# Wi-Fi.net
KiCad netlist of a schematic drawn in Altium Designer
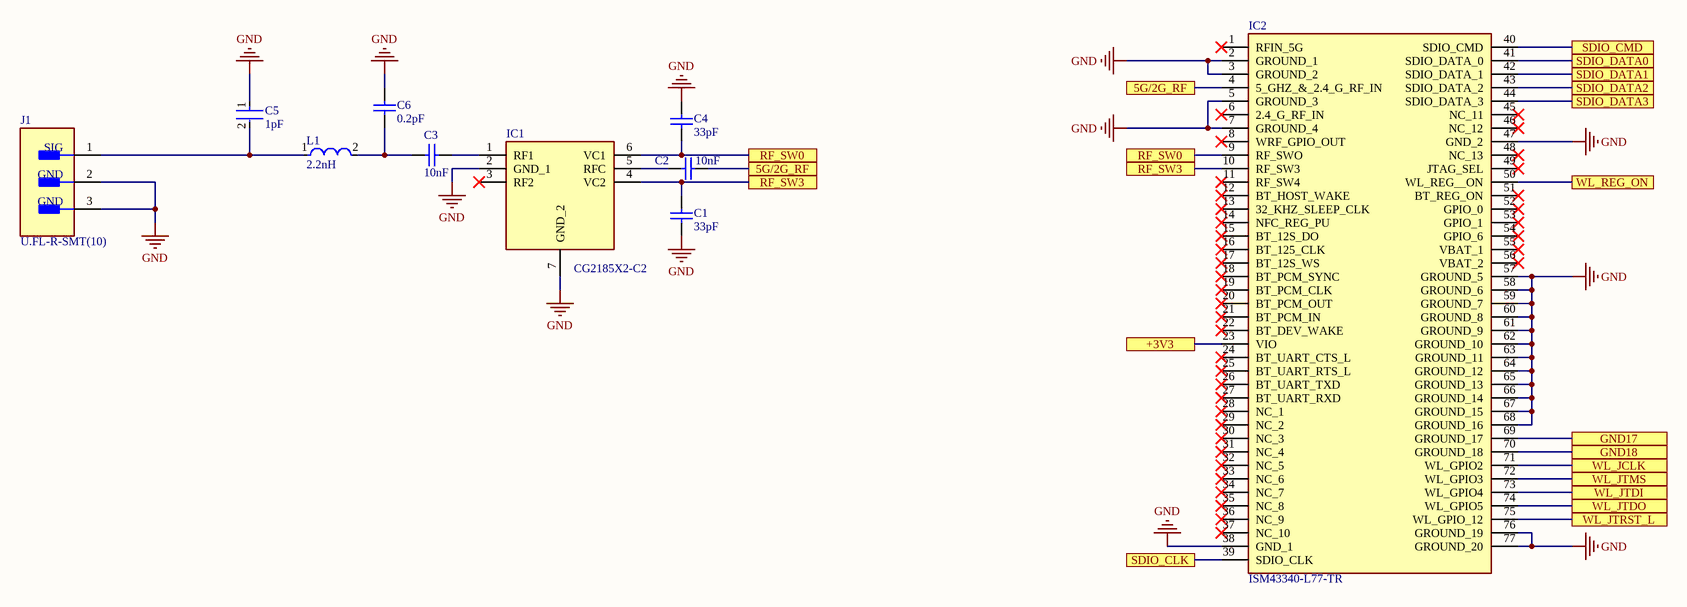
[diagram p0: Wi-Fi.schdoc]

(export (version "E")
  (design (tool "Eeschema 10.0.6"))
  (components
    (comp (ref "C1")
      (value "33pF")
      (footprint "CAPC1005X56X25ML10T15")
      (fields
        (field (name "MANUFACTURER") "AVX Interconnect / Elco")
        (field (name "PART NUMBER") "04025A330JAT2A")
      )
      (libsource (lib "Altium Content Vault") (part "CAP"))
    )
    (comp (ref "C2")
      (value "10nF")
      (footprint "CAPC1608X90X35ML10T15")
      (description "Chip Capacitor, 10 nF, +/- 10%, 50 V, -55 to 125 degC, 0603 (1608 Metric), RoHS, Tape and Reel")
      (fields (field (name "VOLTAGE") "50V") (field (name "TOLERANCE") "10%"))
      (libsource (lib "Altium Content Vault") (part "CAP-NP-2"))
    )
    (comp (ref "C3")
      (value "10nF")
      (footprint "CAPC1608X90X35ML10T15")
      (description "Chip Capacitor, 10 nF, +/- 10%, 50 V, -55 to 125 degC, 0603 (1608 Metric), RoHS, Tape and Reel")
      (fields (field (name "VOLTAGE") "50V") (field (name "TOLERANCE") "10%"))
      (libsource (lib "Altium Content Vault") (part "CAP-NP-2"))
    )
    (comp (ref "C4")
      (value "33pF")
      (footprint "CAPC1005X56X25ML10T15")
      (fields
        (field (name "MANUFACTURER") "AVX Interconnect / Elco")
        (field (name "PART NUMBER") "04025A330JAT2A")
      )
      (libsource (lib "Altium Content Vault") (part "CAP"))
    )
    (comp (ref "C5")
      (value "1pF")
      (footprint "FP-GJM155-0_05-IPC_B")
      (description "Multi-Layer Ceramic Capacitor 1pF C0G  ±0.1pF 0402 Paper T/R")
      (fields (field (name "VOLTAGE") "50V"))
      (libsource (lib "Altium Content Vault") (part "02cd4be3c70576c341d710602a673aa"))
    )
    (comp (ref "C6")
      (value "0.2pF")
      (footprint "CAPC1608X74X38NL10T13")
      (fields
        (field (name "MANUFACTURER") "AVX Interconnect / Elco")
        (field (name "PART NUMBER") "ML03V10R2BAT2A")
      )
      (libsource (lib "Altium Content Vault") (part "CAP"))
    )
    (comp (ref "IC1")
      (value "CG2185X2-C2")
      (footprint "SamacSys:SON35P100X100X37-7N")
      (description "Integrated Circuit")
      (libsource (lib "*") (part "CG2185X2-C2"))
    )
    (comp (ref "IC2")
      (value "ISM43340-L77-TR")
      (footprint "SamacSys:ISM43340L77TR")
      (description "Integrated Circuit")
      (fields (field (name "MOUSER PART NUMBER") "347-ISM43340L77TR"))
      (libsource (lib "SamacSys") (part "ISM43340-L77-TR"))
    )
    (comp (ref "J1")
      (value "U.FL-R-SMT(10)")
      (footprint "FP-U_FL-R-SMT_10-MFG")
      (description "CONN U.FL RCPT STR 50 OHM SMD")
      (libsource (lib "Altium Content Vault") (part "eef6fde44c591823e8076210edfe12f"))
    )
    (comp (ref "L1")
      (value "2.2nH")
      (footprint "FP-LQW15AN_00-W0_6-0_1-MFG")
      (description "Wire Wound RF Inductor 2.2nH ±0.2nH 1000mA 0.027Ω 0402 (1005)")
      (libsource (lib "Altium Content Vault") (part "725321dda6339637d4d059423bc1c3c"))
    )
  )
  (nets
    (net (code "1") (name "/+3V3") (class "Default")
      (node (ref "IC2") (pin "23") (pinfunction "VIO_23") (pintype "passive"))
    )
    (net (code "2") (name "/5G{slash}2G_RF") (class "Default")
      (node (ref "C2") (pin "2") (pinfunction "2_2") (pintype "passive"))
      (node (ref "IC2") (pin "4") (pinfunction "5_GHZ_&_2.4_G_RF_IN_4") (pintype "passive"))
    )
    (net (code "3") (name "/GND17") (class "Default")
      (node (ref "IC2") (pin "69") (pinfunction "GROUND_17_69") (pintype "passive"))
    )
    (net (code "4") (name "/GND18") (class "Default")
      (node (ref "IC2") (pin "70") (pinfunction "GROUND_18_70") (pintype "passive"))
    )
    (net (code "5") (name "/RF_SW0") (class "Default")
      (node (ref "C4") (pin "1") (pinfunction "1_1") (pintype "passive"))
      (node (ref "IC1") (pin "6") (pinfunction "VC1_6") (pintype "passive"))
      (node (ref "IC2") (pin "9") (pinfunction "RF_SWO_9") (pintype "passive"))
    )
    (net (code "6") (name "/RF_SW3") (class "Default")
      (node (ref "C1") (pin "2") (pinfunction "2_2") (pintype "passive"))
      (node (ref "IC1") (pin "4") (pinfunction "VC2_4") (pintype "passive"))
      (node (ref "IC2") (pin "10") (pinfunction "RF_SW3_10") (pintype "passive"))
    )
    (net (code "7") (name "/SDIO_CLK") (class "Default")
      (node (ref "IC2") (pin "39") (pinfunction "SDIO_CLK_39") (pintype "passive"))
    )
    (net (code "8") (name "/SDIO_CMD") (class "Default")
      (node (ref "IC2") (pin "40") (pinfunction "SDIO_CMD_40") (pintype "passive"))
    )
    (net (code "9") (name "/SDIO_DATA0") (class "Default")
      (node (ref "IC2") (pin "41") (pinfunction "SDIO_DATA_0_41") (pintype "passive"))
    )
    (net (code "10") (name "/SDIO_DATA1") (class "Default")
      (node (ref "IC2") (pin "42") (pinfunction "SDIO_DATA_1_42") (pintype "passive"))
    )
    (net (code "11") (name "/SDIO_DATA2") (class "Default")
      (node (ref "IC2") (pin "43") (pinfunction "SDIO_DATA_2_43") (pintype "passive"))
    )
    (net (code "12") (name "/SDIO_DATA3") (class "Default")
      (node (ref "IC2") (pin "44") (pinfunction "SDIO_DATA_3_44") (pintype "passive"))
    )
    (net (code "13") (name "/WL_JCLK") (class "Default")
      (node (ref "IC2") (pin "71") (pinfunction "WL_GPIO2_71") (pintype "passive"))
    )
    (net (code "14") (name "/WL_JTDI") (class "Default")
      (node (ref "IC2") (pin "73") (pinfunction "WL_GPIO4_73") (pintype "passive"))
    )
    (net (code "15") (name "/WL_JTDO") (class "Default")
      (node (ref "IC2") (pin "74") (pinfunction "WL_GPIO5_74") (pintype "passive"))
    )
    (net (code "16") (name "/WL_JTMS") (class "Default")
      (node (ref "IC2") (pin "72") (pinfunction "WL_GPIO3_72") (pintype "passive"))
    )
    (net (code "17") (name "/WL_JTRST_L") (class "Default")
      (node (ref "IC2") (pin "75") (pinfunction "WL_GPIO_12_75") (pintype "passive"))
    )
    (net (code "18") (name "/WL_REG_ON") (class "Default")
      (node (ref "IC2") (pin "50") (pinfunction "WL_REG__ON_50") (pintype "passive"))
    )
    (net (code "19") (name "GND") (class "Default")
      (node (ref "C1") (pin "1") (pinfunction "1_1") (pintype "passive"))
      (node (ref "C4") (pin "2") (pinfunction "2_2") (pintype "passive"))
      (node (ref "C5") (pin "1") (pinfunction "1_1") (pintype "passive"))
      (node (ref "C6") (pin "2") (pinfunction "2_2") (pintype "passive"))
      (node (ref "IC1") (pin "2") (pinfunction "GND_1_2") (pintype "passive"))
      (node (ref "IC1") (pin "7") (pinfunction "GND_2_7") (pintype "passive"))
      (node (ref "IC2") (pin "2") (pinfunction "GROUND_1_2") (pintype "passive"))
      (node (ref "IC2") (pin "3") (pinfunction "GROUND_2_3") (pintype "passive"))
      (node (ref "IC2") (pin "38") (pinfunction "GND_1_38") (pintype "passive"))
      (node (ref "IC2") (pin "47") (pinfunction "GND_2_47") (pintype "passive"))
      (node (ref "IC2") (pin "5") (pinfunction "GROUND_3_5") (pintype "passive"))
      (node (ref "IC2") (pin "57") (pinfunction "GROUND_5_57") (pintype "passive"))
      (node (ref "IC2") (pin "58") (pinfunction "GROUND_6_58") (pintype "passive"))
      (node (ref "IC2") (pin "59") (pinfunction "GROUND_7_59") (pintype "passive"))
      (node (ref "IC2") (pin "60") (pinfunction "GROUND_8_60") (pintype "passive"))
      (node (ref "IC2") (pin "61") (pinfunction "GROUND_9_61") (pintype "passive"))
      (node (ref "IC2") (pin "62") (pinfunction "GROUND_10_62") (pintype "passive"))
      (node (ref "IC2") (pin "63") (pinfunction "GROUND_11_63") (pintype "passive"))
      (node (ref "IC2") (pin "64") (pinfunction "GROUND_12_64") (pintype "passive"))
      (node (ref "IC2") (pin "65") (pinfunction "GROUND_13_65") (pintype "passive"))
      (node (ref "IC2") (pin "66") (pinfunction "GROUND_14_66") (pintype "passive"))
      (node (ref "IC2") (pin "67") (pinfunction "GROUND_15_67") (pintype "passive"))
      (node (ref "IC2") (pin "68") (pinfunction "GROUND_16_68") (pintype "passive"))
      (node (ref "IC2") (pin "7") (pinfunction "GROUND_4_7") (pintype "passive"))
      (node (ref "IC2") (pin "76") (pinfunction "GROUND_19_76") (pintype "passive"))
      (node (ref "IC2") (pin "77") (pinfunction "GROUND_20_77") (pintype "passive"))
      (node (ref "J1") (pin "2") (pinfunction "GND_2") (pintype "power_in"))
      (node (ref "J1") (pin "3") (pinfunction "GND_3") (pintype "power_in"))
    )
    (net (code "20") (name "Net-(C3-Pad1)") (class "Default")
      (node (ref "C3") (pin "1") (pinfunction "1_1") (pintype "passive"))
      (node (ref "C6") (pin "1") (pinfunction "1_1") (pintype "passive"))
      (node (ref "L1") (pin "2") (pinfunction "2_2") (pintype "passive"))
    )
    (net (code "21") (name "Net-(IC1-RF1)") (class "Default")
      (node (ref "C3") (pin "2") (pinfunction "2_2") (pintype "passive"))
      (node (ref "IC1") (pin "1") (pinfunction "RF1_1") (pintype "passive"))
    )
    (net (code "22") (name "Net-(IC1-RFC)") (class "Default")
      (node (ref "C2") (pin "1") (pinfunction "1_1") (pintype "passive"))
      (node (ref "IC1") (pin "5") (pinfunction "RFC_5") (pintype "passive"))
    )
    (net (code "23") (name "Net-(J1-SIG)") (class "Default")
      (node (ref "C5") (pin "2") (pinfunction "2_2") (pintype "passive"))
      (node (ref "J1") (pin "1") (pinfunction "SIG_1") (pintype "passive"))
      (node (ref "L1") (pin "1") (pinfunction "1_1") (pintype "passive"))
    )
    (net (code "24") (name "unconnected-(IC1-RF2-Pad3)") (class "Default")
      (node (ref "IC1") (pin "3") (pinfunction "RF2_3") (pintype "passive+no_connect"))
    )
    (net (code "25") (name "unconnected-(IC2-2.4_G_RF_IN-Pad6)") (class "Default")
      (node (ref "IC2") (pin "6") (pinfunction "2.4_G_RF_IN_6") (pintype "passive+no_connect"))
    )
    (net (code "26") (name "unconnected-(IC2-32_KHZ_SLEEP_CLK-Pad13)") (class "Default")
      (node (ref "IC2") (pin "13") (pinfunction "32_KHZ_SLEEP_CLK_13") (pintype "passive+no_connect"))
    )
    (net (code "27") (name "unconnected-(IC2-BT_12S_DO-Pad15)") (class "Default")
      (node (ref "IC2") (pin "15") (pinfunction "BT_12S_DO_15") (pintype "passive+no_connect"))
    )
    (net (code "28") (name "unconnected-(IC2-BT_12S_WS-Pad17)") (class "Default")
      (node (ref "IC2") (pin "17") (pinfunction "BT_12S_WS_17") (pintype "passive+no_connect"))
    )
    (net (code "29") (name "unconnected-(IC2-BT_125_CLK-Pad16)") (class "Default")
      (node (ref "IC2") (pin "16") (pinfunction "BT_125_CLK_16") (pintype "passive+no_connect"))
    )
    (net (code "30") (name "unconnected-(IC2-BT_DEV_WAKE-Pad22)") (class "Default")
      (node (ref "IC2") (pin "22") (pinfunction "BT_DEV_WAKE_22") (pintype "passive+no_connect"))
    )
    (net (code "31") (name "unconnected-(IC2-BT_HOST_WAKE-Pad12)") (class "Default")
      (node (ref "IC2") (pin "12") (pinfunction "BT_HOST_WAKE_12") (pintype "passive+no_connect"))
    )
    (net (code "32") (name "unconnected-(IC2-BT_PCM_CLK-Pad19)") (class "Default")
      (node (ref "IC2") (pin "19") (pinfunction "BT_PCM_CLK_19") (pintype "passive+no_connect"))
    )
    (net (code "33") (name "unconnected-(IC2-BT_PCM_IN-Pad21)") (class "Default")
      (node (ref "IC2") (pin "21") (pinfunction "BT_PCM_IN_21") (pintype "passive+no_connect"))
    )
    (net (code "34") (name "unconnected-(IC2-BT_PCM_OUT-Pad20)") (class "Default")
      (node (ref "IC2") (pin "20") (pinfunction "BT_PCM_OUT_20") (pintype "passive+no_connect"))
    )
    (net (code "35") (name "unconnected-(IC2-BT_PCM_SYNC-Pad18)") (class "Default")
      (node (ref "IC2") (pin "18") (pinfunction "BT_PCM_SYNC_18") (pintype "passive+no_connect"))
    )
    (net (code "36") (name "unconnected-(IC2-BT_REG_ON-Pad51)") (class "Default")
      (node (ref "IC2") (pin "51") (pinfunction "BT_REG_ON_51") (pintype "passive+no_connect"))
    )
    (net (code "37") (name "unconnected-(IC2-BT_UART_CTS_L-Pad24)") (class "Default")
      (node (ref "IC2") (pin "24") (pinfunction "BT_UART_CTS_L_24") (pintype "passive+no_connect"))
    )
    (net (code "38") (name "unconnected-(IC2-BT_UART_RTS_L-Pad25)") (class "Default")
      (node (ref "IC2") (pin "25") (pinfunction "BT_UART_RTS_L_25") (pintype "passive+no_connect"))
    )
    (net (code "39") (name "unconnected-(IC2-BT_UART_RXD-Pad27)") (class "Default")
      (node (ref "IC2") (pin "27") (pinfunction "BT_UART_RXD_27") (pintype "passive+no_connect"))
    )
    (net (code "40") (name "unconnected-(IC2-BT_UART_TXD-Pad26)") (class "Default")
      (node (ref "IC2") (pin "26") (pinfunction "BT_UART_TXD_26") (pintype "passive+no_connect"))
    )
    (net (code "41") (name "unconnected-(IC2-GPIO_0-Pad52)") (class "Default")
      (node (ref "IC2") (pin "52") (pinfunction "GPIO_0_52") (pintype "passive+no_connect"))
    )
    (net (code "42") (name "unconnected-(IC2-GPIO_1-Pad53)") (class "Default")
      (node (ref "IC2") (pin "53") (pinfunction "GPIO_1_53") (pintype "passive+no_connect"))
    )
    (net (code "43") (name "unconnected-(IC2-GPIO_6-Pad54)") (class "Default")
      (node (ref "IC2") (pin "54") (pinfunction "GPIO_6_54") (pintype "passive+no_connect"))
    )
    (net (code "44") (name "unconnected-(IC2-JTAG_SEL-Pad49)") (class "Default")
      (node (ref "IC2") (pin "49") (pinfunction "JTAG_SEL_49") (pintype "passive+no_connect"))
    )
    (net (code "45") (name "unconnected-(IC2-NC_1-Pad28)") (class "Default")
      (node (ref "IC2") (pin "28") (pinfunction "NC_1_28") (pintype "passive+no_connect"))
    )
    (net (code "46") (name "unconnected-(IC2-NC_2-Pad29)") (class "Default")
      (node (ref "IC2") (pin "29") (pinfunction "NC_2_29") (pintype "passive+no_connect"))
    )
    (net (code "47") (name "unconnected-(IC2-NC_3-Pad30)") (class "Default")
      (node (ref "IC2") (pin "30") (pinfunction "NC_3_30") (pintype "passive+no_connect"))
    )
    (net (code "48") (name "unconnected-(IC2-NC_4-Pad31)") (class "Default")
      (node (ref "IC2") (pin "31") (pinfunction "NC_4_31") (pintype "passive+no_connect"))
    )
    (net (code "49") (name "unconnected-(IC2-NC_5-Pad32)") (class "Default")
      (node (ref "IC2") (pin "32") (pinfunction "NC_5_32") (pintype "passive+no_connect"))
    )
    (net (code "50") (name "unconnected-(IC2-NC_6-Pad33)") (class "Default")
      (node (ref "IC2") (pin "33") (pinfunction "NC_6_33") (pintype "passive+no_connect"))
    )
    (net (code "51") (name "unconnected-(IC2-NC_7-Pad34)") (class "Default")
      (node (ref "IC2") (pin "34") (pinfunction "NC_7_34") (pintype "passive+no_connect"))
    )
    (net (code "52") (name "unconnected-(IC2-NC_8-Pad35)") (class "Default")
      (node (ref "IC2") (pin "35") (pinfunction "NC_8_35") (pintype "passive+no_connect"))
    )
    (net (code "53") (name "unconnected-(IC2-NC_9-Pad36)") (class "Default")
      (node (ref "IC2") (pin "36") (pinfunction "NC_9_36") (pintype "passive+no_connect"))
    )
    (net (code "54") (name "unconnected-(IC2-NC_10-Pad37)") (class "Default")
      (node (ref "IC2") (pin "37") (pinfunction "NC_10_37") (pintype "passive+no_connect"))
    )
    (net (code "55") (name "unconnected-(IC2-NC_11-Pad45)") (class "Default")
      (node (ref "IC2") (pin "45") (pinfunction "NC_11_45") (pintype "passive+no_connect"))
    )
    (net (code "56") (name "unconnected-(IC2-NC_12-Pad46)") (class "Default")
      (node (ref "IC2") (pin "46") (pinfunction "NC_12_46") (pintype "passive+no_connect"))
    )
    (net (code "57") (name "unconnected-(IC2-NC_13-Pad48)") (class "Default")
      (node (ref "IC2") (pin "48") (pinfunction "NC_13_48") (pintype "passive+no_connect"))
    )
    (net (code "58") (name "unconnected-(IC2-NFC_REG_PU-Pad14)") (class "Default")
      (node (ref "IC2") (pin "14") (pinfunction "NFC_REG_PU_14") (pintype "passive+no_connect"))
    )
    (net (code "59") (name "unconnected-(IC2-RFIN_5G-Pad1)") (class "Default")
      (node (ref "IC2") (pin "1") (pinfunction "RFIN_5G_1") (pintype "passive+no_connect"))
    )
    (net (code "60") (name "unconnected-(IC2-RF_SW4-Pad11)") (class "Default")
      (node (ref "IC2") (pin "11") (pinfunction "RF_SW4_11") (pintype "passive+no_connect"))
    )
    (net (code "61") (name "unconnected-(IC2-VBAT_1-Pad55)") (class "Default")
      (node (ref "IC2") (pin "55") (pinfunction "VBAT_1_55") (pintype "passive+no_connect"))
    )
    (net (code "62") (name "unconnected-(IC2-VBAT_2-Pad56)") (class "Default")
      (node (ref "IC2") (pin "56") (pinfunction "VBAT_2_56") (pintype "passive+no_connect"))
    )
    (net (code "63") (name "unconnected-(IC2-WRF_GPIO_OUT-Pad8)") (class "Default")
      (node (ref "IC2") (pin "8") (pinfunction "WRF_GPIO_OUT_8") (pintype "passive+no_connect"))
    )
  )
)
